# writecard_better.net
KiCad netlist of a schematic drawn in EAGLE
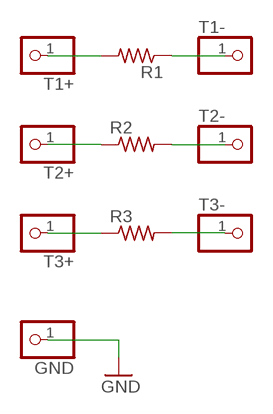
[diagram p0: schematic, sheet 1]

(export (version "E")
  (design (tool "Eeschema 10.0.6"))
  (components
    (comp (ref "GND")
      (value "PINHD-1X1")
      (footprint "eagle-import:1X01")
      (libsource (lib "eagle-import") (part "PINHD-1X1"))
    )
    (comp (ref "R1")
      (value "R-US_R1206")
      (footprint "eagle-import:R1206")
      (libsource (lib "eagle-import") (part "R-US_R1206"))
    )
    (comp (ref "R2")
      (value "R-US_R1206")
      (footprint "eagle-import:R1206")
      (libsource (lib "eagle-import") (part "R-US_R1206"))
    )
    (comp (ref "R3")
      (value "R-US_R1206")
      (footprint "eagle-import:R1206")
      (libsource (lib "eagle-import") (part "R-US_R1206"))
    )
    (comp (ref "T1+")
      (value "PINHD-1X1")
      (footprint "eagle-import:1X01")
      (libsource (lib "eagle-import") (part "PINHD-1X1"))
    )
    (comp (ref "T1-")
      (value "PINHD-1X1")
      (footprint "eagle-import:1X01")
      (libsource (lib "eagle-import") (part "PINHD-1X1"))
    )
    (comp (ref "T2+")
      (value "PINHD-1X1")
      (footprint "eagle-import:1X01")
      (libsource (lib "eagle-import") (part "PINHD-1X1"))
    )
    (comp (ref "T2-")
      (value "PINHD-1X1")
      (footprint "eagle-import:1X01")
      (libsource (lib "eagle-import") (part "PINHD-1X1"))
    )
    (comp (ref "T3+")
      (value "PINHD-1X1")
      (footprint "eagle-import:1X01")
      (libsource (lib "eagle-import") (part "PINHD-1X1"))
    )
    (comp (ref "T3-")
      (value "PINHD-1X1")
      (footprint "eagle-import:1X01")
      (libsource (lib "eagle-import") (part "PINHD-1X1"))
    )
  )
  (nets
    (net (code "1") (name "GND") (class "Default")
      (node (ref "GND") (pin "1") (pinfunction "1_1") (pintype "passive"))
    )
    (net (code "2") (name "Net-(R1-Pad1)") (class "Default")
      (node (ref "R1") (pin "1") (pinfunction "1_1") (pintype "passive"))
      (node (ref "T1-") (pin "1") (pinfunction "1_1") (pintype "passive"))
    )
    (net (code "3") (name "Net-(R1-Pad2)") (class "Default")
      (node (ref "R1") (pin "2") (pinfunction "2_2") (pintype "passive"))
      (node (ref "T1+") (pin "1") (pinfunction "1_1") (pintype "passive"))
    )
    (net (code "4") (name "Net-(R2-Pad1)") (class "Default")
      (node (ref "R2") (pin "1") (pinfunction "1_1") (pintype "passive"))
      (node (ref "T2+") (pin "1") (pinfunction "1_1") (pintype "passive"))
    )
    (net (code "5") (name "Net-(R2-Pad2)") (class "Default")
      (node (ref "R2") (pin "2") (pinfunction "2_2") (pintype "passive"))
      (node (ref "T2-") (pin "1") (pinfunction "1_1") (pintype "passive"))
    )
    (net (code "6") (name "Net-(R3-Pad1)") (class "Default")
      (node (ref "R3") (pin "1") (pinfunction "1_1") (pintype "passive"))
      (node (ref "T3+") (pin "1") (pinfunction "1_1") (pintype "passive"))
    )
    (net (code "7") (name "Net-(R3-Pad2)") (class "Default")
      (node (ref "R3") (pin "2") (pinfunction "2_2") (pintype "passive"))
      (node (ref "T3-") (pin "1") (pinfunction "1_1") (pintype "passive"))
    )
  )
)
